# Sheet.net
KiCad netlist of a schematic drawn in Altium Designer
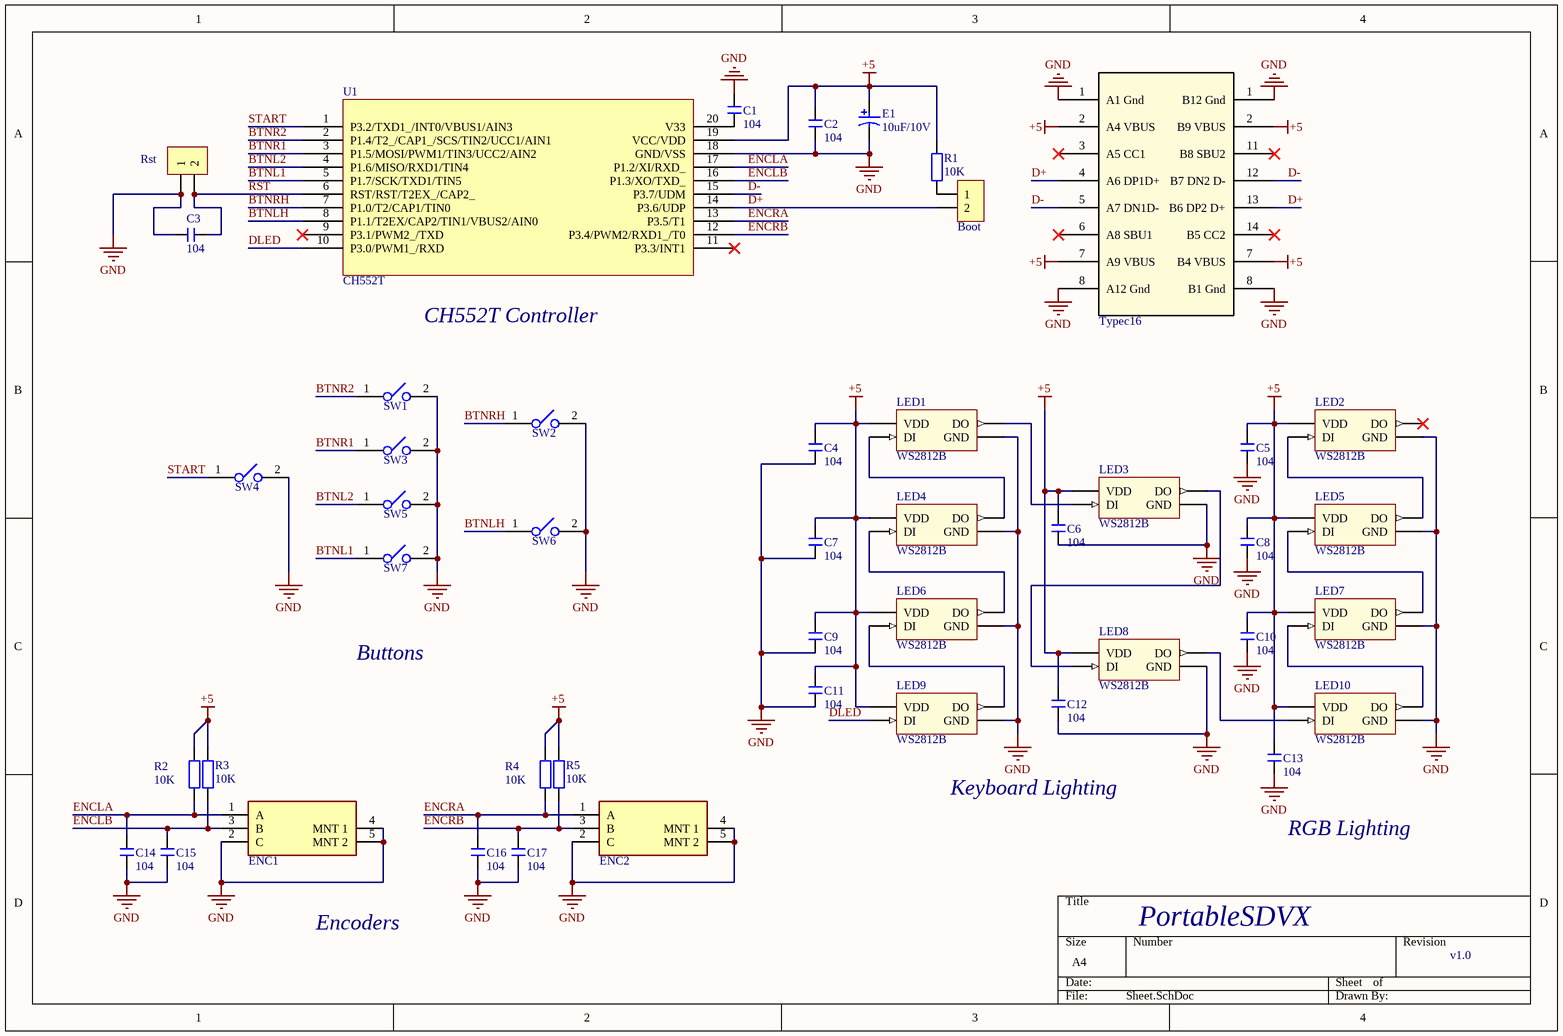
[diagram p0: Sheet.SchDoc]

(export (version "E")
  (design (tool "Eeschema 10.0.6"))
  (components
    (comp (ref "Boot")
      (value "HDR-1X2")
      (footprint "HDR-1X2")
      (description "2P接插件")
      (fields (field (name "版权归属") "源创客"))
      (libsource (lib "Schlib") (part "Header 2"))
    )
    (comp (ref "C1")
      (value "104")
      (footprint "C 0603")
      (description "瓷片电容-贴片")
      (libsource (lib "A") (part "Cap-CER-SMD"))
    )
    (comp (ref "C2")
      (value "104")
      (footprint "C 0603")
      (description "瓷片电容-贴片")
      (libsource (lib "A") (part "Cap-CER-SMD"))
    )
    (comp (ref "C3")
      (value "104")
      (footprint "C 0603")
      (description "无极性贴片电容")
      (fields (field (name "版权归属") "源创客"))
      (libsource (lib "电阻-电容-电感") (part "C"))
    )
    (comp (ref "C4")
      (value "104")
      (footprint "C 0603")
      (description "瓷片电容-贴片")
      (libsource (lib "A") (part "Cap-CER-SMD"))
    )
    (comp (ref "C5")
      (value "104")
      (footprint "C 0603")
      (description "瓷片电容-贴片")
      (libsource (lib "A") (part "Cap-CER-SMD"))
    )
    (comp (ref "C6")
      (value "104")
      (footprint "C 0603")
      (description "瓷片电容-贴片")
      (libsource (lib "A") (part "Cap-CER-SMD"))
    )
    (comp (ref "C7")
      (value "104")
      (footprint "C 0603")
      (description "瓷片电容-贴片")
      (libsource (lib "A") (part "Cap-CER-SMD"))
    )
    (comp (ref "C8")
      (value "104")
      (footprint "C 0603")
      (description "瓷片电容-贴片")
      (libsource (lib "A") (part "Cap-CER-SMD"))
    )
    (comp (ref "C9")
      (value "104")
      (footprint "C 0603")
      (description "瓷片电容-贴片")
      (libsource (lib "A") (part "Cap-CER-SMD"))
    )
    (comp (ref "C10")
      (value "104")
      (footprint "C 0603")
      (description "瓷片电容-贴片")
      (libsource (lib "A") (part "Cap-CER-SMD"))
    )
    (comp (ref "C11")
      (value "104")
      (footprint "C 0603")
      (description "瓷片电容-贴片")
      (libsource (lib "A") (part "Cap-CER-SMD"))
    )
    (comp (ref "C12")
      (value "104")
      (footprint "C 0603")
      (description "瓷片电容-贴片")
      (libsource (lib "A") (part "Cap-CER-SMD"))
    )
    (comp (ref "C13")
      (value "104")
      (footprint "C 0603")
      (description "瓷片电容-贴片")
      (libsource (lib "A") (part "Cap-CER-SMD"))
    )
    (comp (ref "C14")
      (value "104")
      (footprint "C 0603")
      (description "瓷片电容-贴片")
      (libsource (lib "A") (part "Cap-CER-SMD"))
    )
    (comp (ref "C15")
      (value "104")
      (footprint "C 0603")
      (description "瓷片电容-贴片")
      (libsource (lib "A") (part "Cap-CER-SMD"))
    )
    (comp (ref "C16")
      (value "104")
      (footprint "C 0603")
      (description "瓷片电容-贴片")
      (libsource (lib "A") (part "Cap-CER-SMD"))
    )
    (comp (ref "C17")
      (value "104")
      (footprint "C 0603")
      (description "瓷片电容-贴片")
      (libsource (lib "A") (part "Cap-CER-SMD"))
    )
    (comp (ref "E1")
      (value "10uF/10V")
      (footprint "CD B(3528)")
      (description "钽电解电容-贴片")
      (libsource (lib "A") (part "Cap-TAN-SMD"))
    )
    (comp (ref "ENC1")
      (value "EC12E24204A9")
      (footprint "ALPS_EC12E24204A9_MFG")
      (libsource (lib "Schlib") (part "EC12E24204A9"))
    )
    (comp (ref "ENC2")
      (value "EC12E24204A9")
      (footprint "ALPS_EC12E24204A9_MFG")
      (libsource (lib "Schlib") (part "EC12E24204A9"))
    )
    (comp (ref "J1") (value "Typec16") (footprint "typec 16p") (libsource (lib "Schlib") (part "Typec16")))
    (comp (ref "LED1")
      (value "WS2812B")
      (footprint "WS2812_sink")
      (description "Raspberry Pi HAT _40 pin_ Wheeled Robotics Kit")
      (fields (field (name "MF") "SparkFun Electronics"))
      (libsource (lib "Schlib") (part "WS2812B"))
    )
    (comp (ref "LED2")
      (value "WS2812B")
      (footprint "WS2812B")
      (description "Raspberry Pi HAT _40 pin_ Wheeled Robotics Kit")
      (fields (field (name "MF") "SparkFun Electronics"))
      (libsource (lib "Schlib") (part "WS2812B"))
    )
    (comp (ref "LED3")
      (value "WS2812B")
      (footprint "WS2812_sink")
      (description "Raspberry Pi HAT _40 pin_ Wheeled Robotics Kit")
      (fields (field (name "MF") "SparkFun Electronics"))
      (libsource (lib "Schlib") (part "WS2812B"))
    )
    (comp (ref "LED4")
      (value "WS2812B")
      (footprint "WS2812_sink")
      (description "Raspberry Pi HAT _40 pin_ Wheeled Robotics Kit")
      (fields (field (name "MF") "SparkFun Electronics"))
      (libsource (lib "Schlib") (part "WS2812B"))
    )
    (comp (ref "LED5")
      (value "WS2812B")
      (footprint "WS2812B")
      (description "Raspberry Pi HAT _40 pin_ Wheeled Robotics Kit")
      (fields (field (name "MF") "SparkFun Electronics"))
      (libsource (lib "Schlib") (part "WS2812B"))
    )
    (comp (ref "LED6")
      (value "WS2812B")
      (footprint "WS2812_sink")
      (description "Raspberry Pi HAT _40 pin_ Wheeled Robotics Kit")
      (fields (field (name "MF") "SparkFun Electronics"))
      (libsource (lib "Schlib") (part "WS2812B"))
    )
    (comp (ref "LED7")
      (value "WS2812B")
      (footprint "WS2812B")
      (description "Raspberry Pi HAT _40 pin_ Wheeled Robotics Kit")
      (fields (field (name "MF") "SparkFun Electronics"))
      (libsource (lib "Schlib") (part "WS2812B"))
    )
    (comp (ref "LED8")
      (value "WS2812B")
      (footprint "WS2812_sink")
      (description "Raspberry Pi HAT _40 pin_ Wheeled Robotics Kit")
      (fields (field (name "MF") "SparkFun Electronics"))
      (libsource (lib "Schlib") (part "WS2812B"))
    )
    (comp (ref "LED9")
      (value "WS2812B")
      (footprint "WS2812_sink")
      (description "Raspberry Pi HAT _40 pin_ Wheeled Robotics Kit")
      (fields (field (name "MF") "SparkFun Electronics"))
      (libsource (lib "Schlib") (part "WS2812B"))
    )
    (comp (ref "LED10")
      (value "WS2812B")
      (footprint "WS2812B")
      (description "Raspberry Pi HAT _40 pin_ Wheeled Robotics Kit")
      (fields (field (name "MF") "SparkFun Electronics"))
      (libsource (lib "Schlib") (part "WS2812B"))
    )
    (comp (ref "R1")
      (value "10K")
      (footprint "Res-SMD-0603")
      (description "固定电阻器-贴片")
      (libsource (lib "Schlib") (part "Res-Fixed-SMD"))
    )
    (comp (ref "R2")
      (value "10K")
      (footprint "Res-SMD-0603")
      (description "固定电阻器-贴片")
      (libsource (lib "Schlib") (part "Res-Fixed-SMD"))
    )
    (comp (ref "R3")
      (value "10K")
      (footprint "Res-SMD-0603")
      (description "固定电阻器-贴片")
      (libsource (lib "Schlib") (part "Res-Fixed-SMD"))
    )
    (comp (ref "R4")
      (value "10K")
      (footprint "Res-SMD-0603")
      (description "固定电阻器-贴片")
      (libsource (lib "Schlib") (part "Res-Fixed-SMD"))
    )
    (comp (ref "R5")
      (value "10K")
      (footprint "Res-SMD-0603")
      (description "固定电阻器-贴片")
      (libsource (lib "Schlib") (part "Res-Fixed-SMD"))
    )
    (comp (ref "Rst")
      (value "HDR-1X2")
      (footprint "HDR-1X2")
      (description "2P接插件")
      (fields (field (name "版权归属") "源创客"))
      (libsource (lib "") (part "Header 2_1"))
    )
    (comp (ref "SW1")
      (value "SWITCH")
      (footprint "Cherry_MX1A")
      (description "SWITCH Pushbutton Switch SPST-NO Keyswitch Through Hole")
      (fields (field (name "MANUFACTURER") "Cherry") (field (name "MOUSER PART NUMBER") "540-MX1A-11NW"))
      (libsource (lib "Schlib") (part "SWITCH"))
    )
    (comp (ref "SW2")
      (value "SWITCH")
      (footprint "Cherry_MX1A_X2")
      (description "SWITCH Pushbutton Switch SPST-NO Keyswitch Through Hole")
      (fields (field (name "MANUFACTURER") "Cherry") (field (name "MOUSER PART NUMBER") "540-MX1A-11NW"))
      (libsource (lib "Schlib") (part "SWITCH"))
    )
    (comp (ref "SW3")
      (value "SWITCH")
      (footprint "Cherry_MX1A")
      (description "SWITCH Pushbutton Switch SPST-NO Keyswitch Through Hole")
      (fields (field (name "MANUFACTURER") "Cherry") (field (name "MOUSER PART NUMBER") "540-MX1A-11NW"))
      (libsource (lib "Schlib") (part "SWITCH"))
    )
    (comp (ref "SW4")
      (value "SWITCH")
      (footprint "Cherry_MX1A")
      (description "SWITCH Pushbutton Switch SPST-NO Keyswitch Through Hole")
      (fields (field (name "MANUFACTURER") "Cherry") (field (name "MOUSER PART NUMBER") "540-MX1A-11NW"))
      (libsource (lib "Schlib") (part "SWITCH"))
    )
    (comp (ref "SW5")
      (value "SWITCH")
      (footprint "Cherry_MX1A")
      (description "SWITCH Pushbutton Switch SPST-NO Keyswitch Through Hole")
      (fields (field (name "MANUFACTURER") "Cherry") (field (name "MOUSER PART NUMBER") "540-MX1A-11NW"))
      (libsource (lib "Schlib") (part "SWITCH"))
    )
    (comp (ref "SW6")
      (value "SWITCH")
      (footprint "Cherry_MX1A_X2")
      (description "SWITCH Pushbutton Switch SPST-NO Keyswitch Through Hole")
      (fields (field (name "MANUFACTURER") "Cherry") (field (name "MOUSER PART NUMBER") "540-MX1A-11NW"))
      (libsource (lib "Schlib") (part "SWITCH"))
    )
    (comp (ref "SW7")
      (value "SWITCH")
      (footprint "Cherry_MX1A")
      (description "SWITCH Pushbutton Switch SPST-NO Keyswitch Through Hole")
      (fields (field (name "MANUFACTURER") "Cherry") (field (name "MOUSER PART NUMBER") "540-MX1A-11NW"))
      (libsource (lib "Schlib") (part "SWITCH"))
    )
    (comp (ref "U1") (value "CH552T") (footprint "TSSOP20_N") (libsource (lib "Schlib") (part "CH552T")))
  )
  (nets
    (net (code "1") (name "+5") (class "Default")
      (node (ref "C10") (pin "2") (pinfunction "2_2") (pintype "passive"))
      (node (ref "C11") (pin "2") (pinfunction "2_2") (pintype "passive"))
      (node (ref "C12") (pin "2") (pinfunction "2_2") (pintype "passive"))
      (node (ref "C13") (pin "2") (pinfunction "2_2") (pintype "passive"))
      (node (ref "C2") (pin "2") (pinfunction "2_2") (pintype "passive"))
      (node (ref "C4") (pin "2") (pinfunction "2_2") (pintype "passive"))
      (node (ref "C5") (pin "2") (pinfunction "2_2") (pintype "passive"))
      (node (ref "C6") (pin "2") (pinfunction "2_2") (pintype "passive"))
      (node (ref "C7") (pin "2") (pinfunction "2_2") (pintype "passive"))
      (node (ref "C8") (pin "2") (pinfunction "2_2") (pintype "passive"))
      (node (ref "C9") (pin "2") (pinfunction "2_2") (pintype "passive"))
      (node (ref "E1") (pin "A") (pinfunction "A_A") (pintype "passive"))
      (node (ref "J1") (pin "2") (pinfunction "B9_VBUS_2") (pintype "passive"))
      (node (ref "J1") (pin "7") (pinfunction "A9_VBUS_7") (pintype "passive"))
      (node (ref "LED1") (pin "1") (pinfunction "VDD_1") (pintype "power_in"))
      (node (ref "LED10") (pin "1") (pinfunction "VDD_1") (pintype "power_in"))
      (node (ref "LED2") (pin "1") (pinfunction "VDD_1") (pintype "power_in"))
      (node (ref "LED3") (pin "1") (pinfunction "VDD_1") (pintype "power_in"))
      (node (ref "LED4") (pin "1") (pinfunction "VDD_1") (pintype "power_in"))
      (node (ref "LED5") (pin "1") (pinfunction "VDD_1") (pintype "power_in"))
      (node (ref "LED6") (pin "1") (pinfunction "VDD_1") (pintype "power_in"))
      (node (ref "LED7") (pin "1") (pinfunction "VDD_1") (pintype "power_in"))
      (node (ref "LED8") (pin "1") (pinfunction "VDD_1") (pintype "power_in"))
      (node (ref "LED9") (pin "1") (pinfunction "VDD_1") (pintype "power_in"))
      (node (ref "R1") (pin "2") (pinfunction "2_2") (pintype "passive"))
      (node (ref "R2") (pin "2") (pinfunction "2_2") (pintype "passive"))
      (node (ref "R3") (pin "2") (pinfunction "2_2") (pintype "passive"))
      (node (ref "R4") (pin "2") (pinfunction "2_2") (pintype "passive"))
      (node (ref "R5") (pin "2") (pinfunction "2_2") (pintype "passive"))
      (node (ref "U1") (pin "19") (pinfunction "VCC/VDD_19") (pintype "passive"))
    )
    (net (code "2") (name "/BTNL1") (class "Default")
      (node (ref "SW7") (pin "1") (pinfunction "1_1") (pintype "passive"))
      (node (ref "U1") (pin "5") (pinfunction "P1.7/SCK/TXD1/TIN5_5") (pintype "passive"))
    )
    (net (code "3") (name "/BTNL2") (class "Default")
      (node (ref "SW5") (pin "1") (pinfunction "1_1") (pintype "passive"))
      (node (ref "U1") (pin "4") (pinfunction "P1.6/MISO/RXD1/TIN4_4") (pintype "passive"))
    )
    (net (code "4") (name "/BTNLH") (class "Default")
      (node (ref "SW6") (pin "1") (pinfunction "1_1") (pintype "passive"))
      (node (ref "U1") (pin "8") (pinfunction "P1.1/T2EX/CAP2/TIN1/VBUS2/AIN0_8") (pintype "passive"))
    )
    (net (code "5") (name "/BTNR1") (class "Default")
      (node (ref "SW3") (pin "1") (pinfunction "1_1") (pintype "passive"))
      (node (ref "U1") (pin "3") (pinfunction "P1.5/MOSI/PWM1/TIN3/UCC2/AIN2_3") (pintype "passive"))
    )
    (net (code "6") (name "/BTNR2") (class "Default")
      (node (ref "SW1") (pin "1") (pinfunction "1_1") (pintype "passive"))
      (node (ref "U1") (pin "2") (pinfunction "P1.4/T2_/CAP1_/SCS/TIN2/UCC1/AIN1_2") (pintype "passive"))
    )
    (net (code "7") (name "/BTNRH") (class "Default")
      (node (ref "SW2") (pin "1") (pinfunction "1_1") (pintype "passive"))
      (node (ref "U1") (pin "7") (pinfunction "P1.0/T2/CAP1/TIN0_7") (pintype "passive"))
    )
    (net (code "8") (name "/D+") (class "Default")
      (node (ref "Boot") (pin "2") (pinfunction "2_2") (pintype "passive"))
      (node (ref "J1") (pin "13") (pinfunction "B6_DP2_D+_13") (pintype "passive"))
      (node (ref "J1") (pin "4") (pinfunction "A6_DP1D+_4") (pintype "passive"))
      (node (ref "U1") (pin "14") (pinfunction "P3.6/UDP_14") (pintype "passive"))
    )
    (net (code "9") (name "/D-") (class "Default")
      (node (ref "J1") (pin "12") (pinfunction "B7_DN2_D-_12") (pintype "passive"))
      (node (ref "J1") (pin "5") (pinfunction "A7_DN1D-_5") (pintype "passive"))
      (node (ref "U1") (pin "15") (pinfunction "P3.7/UDM_15") (pintype "passive"))
    )
    (net (code "10") (name "/DLED") (class "Default")
      (node (ref "LED9") (pin "4") (pinfunction "DI_4") (pintype "input"))
      (node (ref "U1") (pin "10") (pinfunction "P3.0/PWM1_/RXD_10") (pintype "passive"))
    )
    (net (code "11") (name "/ENCLA") (class "Default")
      (node (ref "C14") (pin "2") (pinfunction "2_2") (pintype "passive"))
      (node (ref "ENC1") (pin "1") (pinfunction "A_1") (pintype "passive"))
      (node (ref "R2") (pin "1") (pinfunction "1_1") (pintype "passive"))
      (node (ref "U1") (pin "17") (pinfunction "P1.2/XI/RXD__17") (pintype "passive"))
    )
    (net (code "12") (name "/ENCLB") (class "Default")
      (node (ref "C15") (pin "2") (pinfunction "2_2") (pintype "passive"))
      (node (ref "ENC1") (pin "3") (pinfunction "B_3") (pintype "passive"))
      (node (ref "R3") (pin "1") (pinfunction "1_1") (pintype "passive"))
      (node (ref "U1") (pin "16") (pinfunction "P1.3/XO/TXD__16") (pintype "passive"))
    )
    (net (code "13") (name "/ENCRA") (class "Default")
      (node (ref "C16") (pin "2") (pinfunction "2_2") (pintype "passive"))
      (node (ref "ENC2") (pin "1") (pinfunction "A_1") (pintype "passive"))
      (node (ref "R4") (pin "1") (pinfunction "1_1") (pintype "passive"))
      (node (ref "U1") (pin "13") (pinfunction "P3.5/T1_13") (pintype "passive"))
    )
    (net (code "14") (name "/ENCRB") (class "Default")
      (node (ref "C17") (pin "2") (pinfunction "2_2") (pintype "passive"))
      (node (ref "ENC2") (pin "3") (pinfunction "B_3") (pintype "passive"))
      (node (ref "R5") (pin "1") (pinfunction "1_1") (pintype "passive"))
      (node (ref "U1") (pin "12") (pinfunction "P3.4/PWM2/RXD1_/T0_12") (pintype "passive"))
    )
    (net (code "15") (name "/RST") (class "Default")
      (node (ref "C3") (pin "2") (pinfunction "2_2") (pintype "passive"))
      (node (ref "Rst") (pin "2") (pinfunction "2_2") (pintype "passive"))
      (node (ref "U1") (pin "6") (pinfunction "RST/RST/T2EX_/CAP2__6") (pintype "passive"))
    )
    (net (code "16") (name "/START") (class "Default")
      (node (ref "SW4") (pin "1") (pinfunction "1_1") (pintype "passive"))
      (node (ref "U1") (pin "1") (pinfunction "P3.2/TXD1_/INT0/VBUS1/AIN3_1") (pintype "passive"))
    )
    (net (code "17") (name "GND") (class "Default")
      (node (ref "C1") (pin "2") (pinfunction "2_2") (pintype "passive"))
      (node (ref "C10") (pin "1") (pinfunction "1_1") (pintype "passive"))
      (node (ref "C11") (pin "1") (pinfunction "1_1") (pintype "passive"))
      (node (ref "C12") (pin "1") (pinfunction "1_1") (pintype "passive"))
      (node (ref "C13") (pin "1") (pinfunction "1_1") (pintype "passive"))
      (node (ref "C14") (pin "1") (pinfunction "1_1") (pintype "passive"))
      (node (ref "C15") (pin "1") (pinfunction "1_1") (pintype "passive"))
      (node (ref "C16") (pin "1") (pinfunction "1_1") (pintype "passive"))
      (node (ref "C17") (pin "1") (pinfunction "1_1") (pintype "passive"))
      (node (ref "C2") (pin "1") (pinfunction "1_1") (pintype "passive"))
      (node (ref "C3") (pin "1") (pinfunction "1_1") (pintype "passive"))
      (node (ref "C4") (pin "1") (pinfunction "1_1") (pintype "passive"))
      (node (ref "C5") (pin "1") (pinfunction "1_1") (pintype "passive"))
      (node (ref "C6") (pin "1") (pinfunction "1_1") (pintype "passive"))
      (node (ref "C7") (pin "1") (pinfunction "1_1") (pintype "passive"))
      (node (ref "C8") (pin "1") (pinfunction "1_1") (pintype "passive"))
      (node (ref "C9") (pin "1") (pinfunction "1_1") (pintype "passive"))
      (node (ref "E1") (pin "K") (pinfunction "K_K") (pintype "passive"))
      (node (ref "ENC1") (pin "2") (pinfunction "C_2") (pintype "passive"))
      (node (ref "ENC1") (pin "4") (pinfunction "MNT_1_4") (pintype "passive"))
      (node (ref "ENC1") (pin "5") (pinfunction "MNT_2_5") (pintype "passive"))
      (node (ref "ENC2") (pin "2") (pinfunction "C_2") (pintype "passive"))
      (node (ref "ENC2") (pin "4") (pinfunction "MNT_1_4") (pintype "passive"))
      (node (ref "ENC2") (pin "5") (pinfunction "MNT_2_5") (pintype "passive"))
      (node (ref "J1") (pin "1") (pinfunction "B12_Gnd_1") (pintype "passive"))
      (node (ref "J1") (pin "8") (pinfunction "B1_Gnd_8") (pintype "passive"))
      (node (ref "LED1") (pin "3") (pinfunction "GND_3") (pintype "power_in"))
      (node (ref "LED10") (pin "3") (pinfunction "GND_3") (pintype "power_in"))
      (node (ref "LED2") (pin "3") (pinfunction "GND_3") (pintype "power_in"))
      (node (ref "LED3") (pin "3") (pinfunction "GND_3") (pintype "power_in"))
      (node (ref "LED4") (pin "3") (pinfunction "GND_3") (pintype "power_in"))
      (node (ref "LED5") (pin "3") (pinfunction "GND_3") (pintype "power_in"))
      (node (ref "LED6") (pin "3") (pinfunction "GND_3") (pintype "power_in"))
      (node (ref "LED7") (pin "3") (pinfunction "GND_3") (pintype "power_in"))
      (node (ref "LED8") (pin "3") (pinfunction "GND_3") (pintype "power_in"))
      (node (ref "LED9") (pin "3") (pinfunction "GND_3") (pintype "power_in"))
      (node (ref "Rst") (pin "1") (pinfunction "1_1") (pintype "passive"))
      (node (ref "SW1") (pin "2") (pinfunction "2_2") (pintype "passive"))
      (node (ref "SW2") (pin "2") (pinfunction "2_2") (pintype "passive"))
      (node (ref "SW3") (pin "2") (pinfunction "2_2") (pintype "passive"))
      (node (ref "SW4") (pin "2") (pinfunction "2_2") (pintype "passive"))
      (node (ref "SW5") (pin "2") (pinfunction "2_2") (pintype "passive"))
      (node (ref "SW6") (pin "2") (pinfunction "2_2") (pintype "passive"))
      (node (ref "SW7") (pin "2") (pinfunction "2_2") (pintype "passive"))
      (node (ref "U1") (pin "18") (pinfunction "GND/VSS_18") (pintype "passive"))
    )
    (net (code "18") (name "Net-(Boot-Pad1)") (class "Default")
      (node (ref "Boot") (pin "1") (pinfunction "1_1") (pintype "passive"))
      (node (ref "R1") (pin "1") (pinfunction "1_1") (pintype "passive"))
    )
    (net (code "19") (name "Net-(LED1-DI)") (class "Default")
      (node (ref "LED1") (pin "4") (pinfunction "DI_4") (pintype "input"))
      (node (ref "LED4") (pin "2") (pinfunction "DO_2") (pintype "output"))
    )
    (net (code "20") (name "Net-(LED1-DO)") (class "Default")
      (node (ref "LED1") (pin "2") (pinfunction "DO_2") (pintype "output"))
      (node (ref "LED3") (pin "4") (pinfunction "DI_4") (pintype "input"))
    )
    (net (code "21") (name "Net-(LED2-DI)") (class "Default")
      (node (ref "LED2") (pin "4") (pinfunction "DI_4") (pintype "input"))
      (node (ref "LED5") (pin "2") (pinfunction "DO_2") (pintype "output"))
    )
    (net (code "22") (name "Net-(LED3-DO)") (class "Default")
      (node (ref "LED3") (pin "2") (pinfunction "DO_2") (pintype "output"))
      (node (ref "LED8") (pin "4") (pinfunction "DI_4") (pintype "input"))
    )
    (net (code "23") (name "Net-(LED4-DI)") (class "Default")
      (node (ref "LED4") (pin "4") (pinfunction "DI_4") (pintype "input"))
      (node (ref "LED6") (pin "2") (pinfunction "DO_2") (pintype "output"))
    )
    (net (code "24") (name "Net-(LED5-DI)") (class "Default")
      (node (ref "LED5") (pin "4") (pinfunction "DI_4") (pintype "input"))
      (node (ref "LED7") (pin "2") (pinfunction "DO_2") (pintype "output"))
    )
    (net (code "25") (name "Net-(LED6-DI)") (class "Default")
      (node (ref "LED6") (pin "4") (pinfunction "DI_4") (pintype "input"))
      (node (ref "LED9") (pin "2") (pinfunction "DO_2") (pintype "output"))
    )
    (net (code "26") (name "Net-(LED10-DI)") (class "Default")
      (node (ref "LED10") (pin "4") (pinfunction "DI_4") (pintype "input"))
      (node (ref "LED8") (pin "2") (pinfunction "DO_2") (pintype "output"))
    )
    (net (code "27") (name "Net-(LED10-DO)") (class "Default")
      (node (ref "LED10") (pin "2") (pinfunction "DO_2") (pintype "output"))
      (node (ref "LED7") (pin "4") (pinfunction "DI_4") (pintype "input"))
    )
    (net (code "28") (name "Net-(U1-V33)") (class "Default")
      (node (ref "C1") (pin "1") (pinfunction "1_1") (pintype "passive"))
      (node (ref "U1") (pin "20") (pinfunction "V33_20") (pintype "passive"))
    )
    (net (code "29") (name "unconnected-(J1-A5_CC1-Pad3)") (class "Default")
      (node (ref "J1") (pin "3") (pinfunction "A5_CC1_3") (pintype "passive+no_connect"))
    )
    (net (code "30") (name "unconnected-(J1-A8_SBU1-Pad6)") (class "Default")
      (node (ref "J1") (pin "6") (pinfunction "A8_SBU1_6") (pintype "passive+no_connect"))
    )
    (net (code "31") (name "unconnected-(J1-B5_CC2-Pad14)") (class "Default")
      (node (ref "J1") (pin "14") (pinfunction "B5_CC2_14") (pintype "passive+no_connect"))
    )
    (net (code "32") (name "unconnected-(J1-B8_SBU2-Pad11)") (class "Default")
      (node (ref "J1") (pin "11") (pinfunction "B8_SBU2_11") (pintype "passive+no_connect"))
    )
    (net (code "33") (name "unconnected-(LED2-DO-Pad2)") (class "Default")
      (node (ref "LED2") (pin "2") (pinfunction "DO_2") (pintype "output+no_connect"))
    )
    (net (code "34") (name "unconnected-(U1-P3.1{slash}PWM2_{slash}TXD-Pad9)") (class "Default")
      (node (ref "U1") (pin "9") (pinfunction "P3.1/PWM2_/TXD_9") (pintype "passive+no_connect"))
    )
    (net (code "35") (name "unconnected-(U1-P3.3{slash}INT1-Pad11)") (class "Default")
      (node (ref "U1") (pin "11") (pinfunction "P3.3/INT1_11") (pintype "passive+no_connect"))
    )
  )
)
